# corex.net
KiCad netlist of a schematic drawn in EAGLE
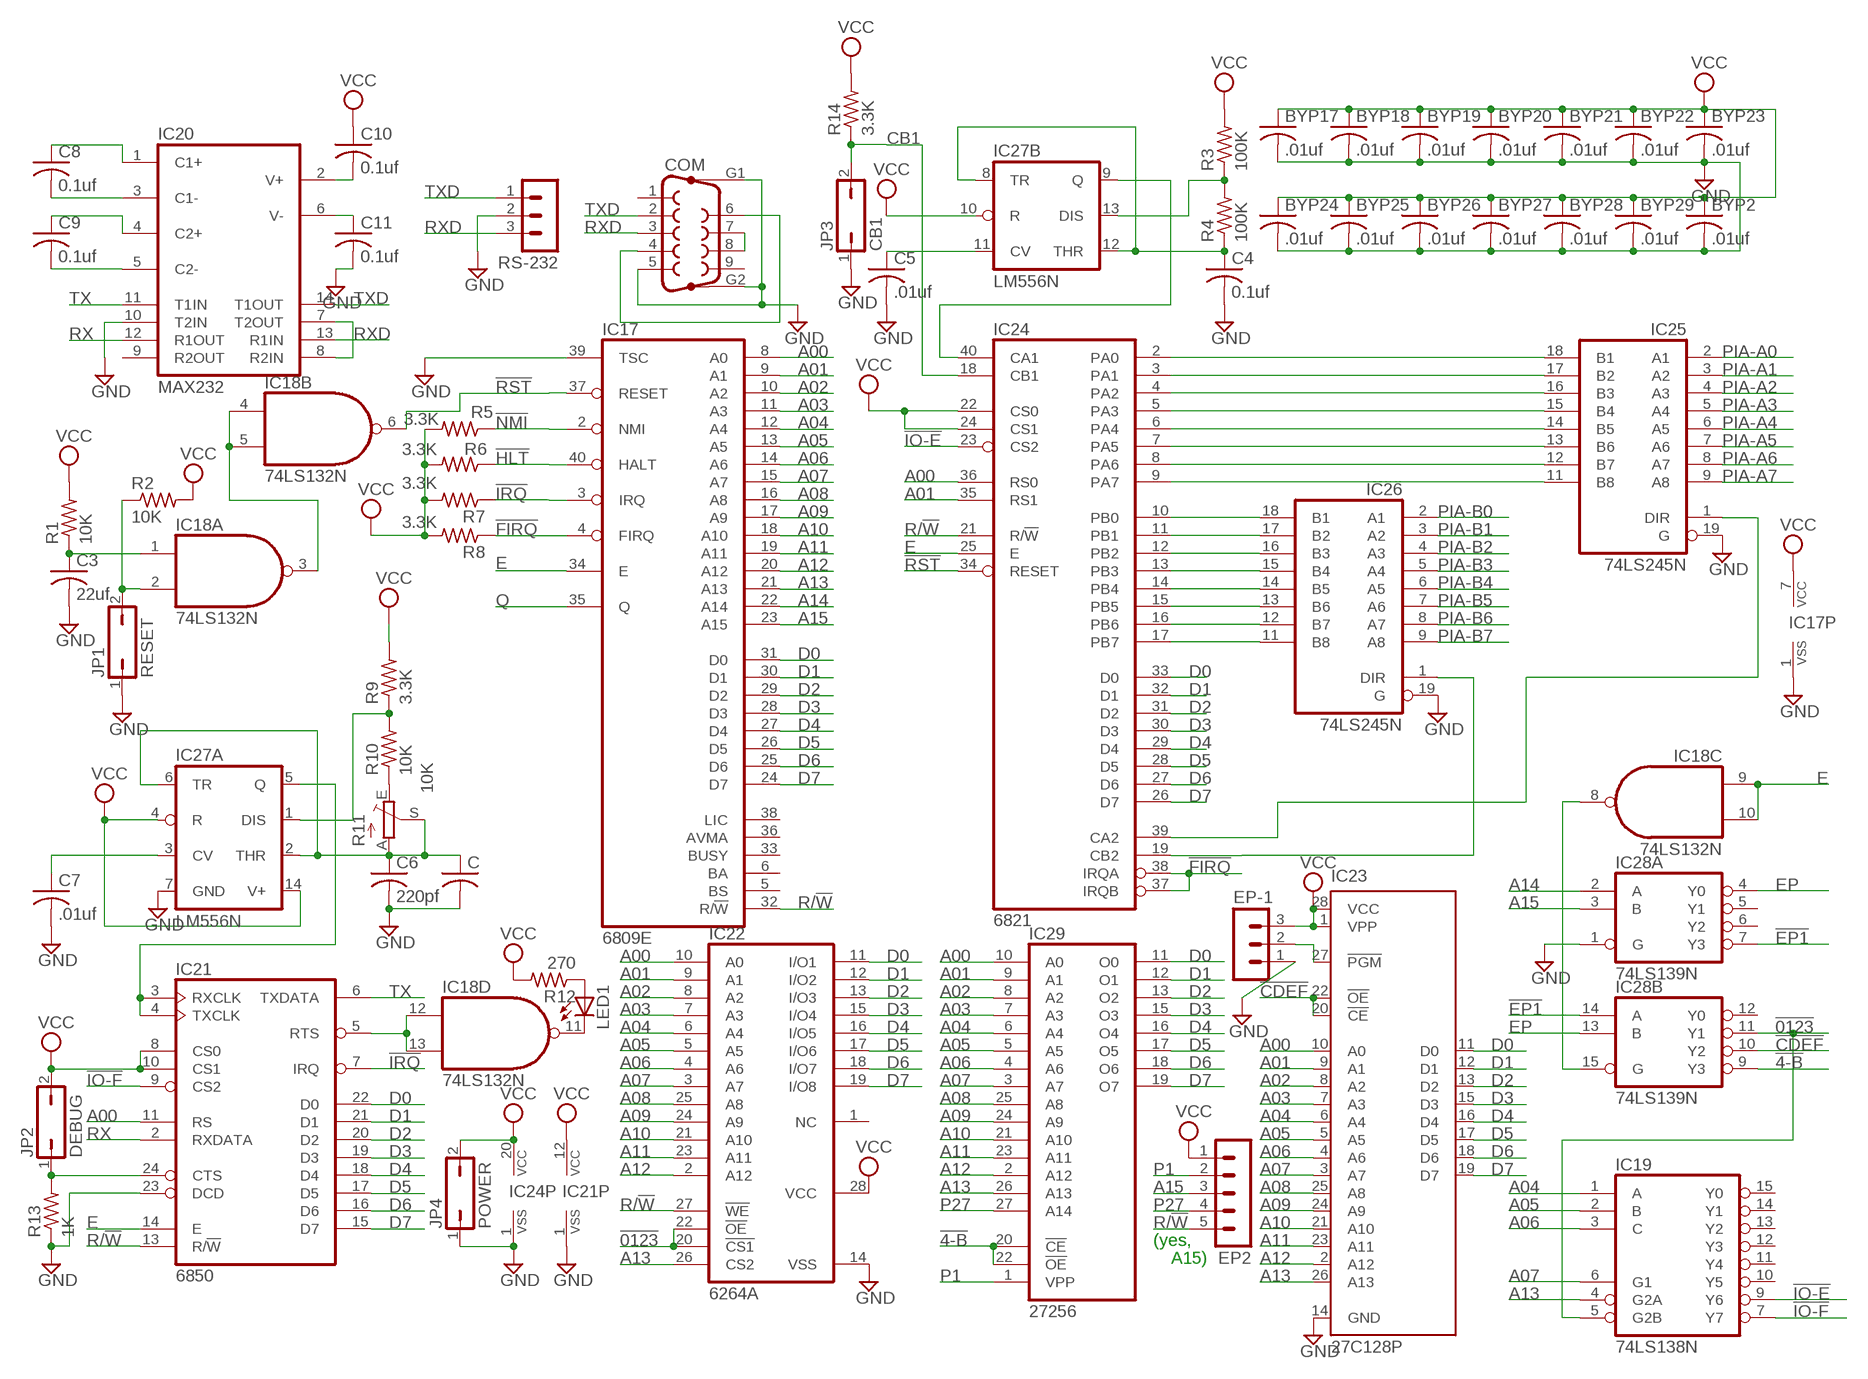
[diagram p0: schematic, sheet 1]
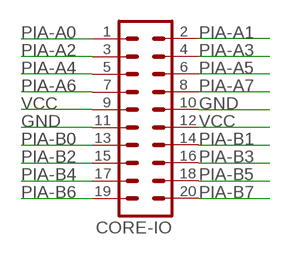
[diagram p1: schematic, sheet 2]
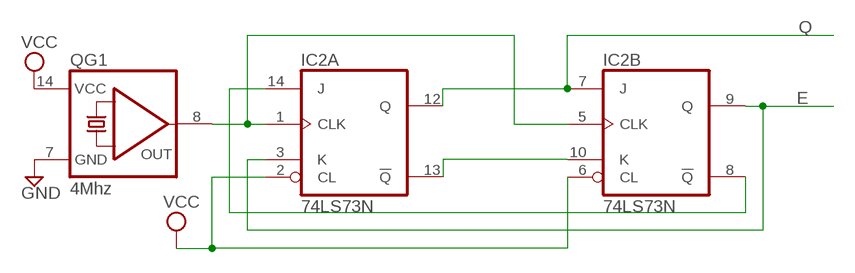
[diagram p2: schematic, sheet 3]

(export (version "E")
  (design (tool "Eeschema 10.0.6"))
  (components
    (comp (ref "IC2")
      (value "74LS73N")
      (footprint "eagle-import:DIL14")
      (libsource (lib "eagle-import") (part "7473NLS"))
    )
    (comp (ref "QG1")
      (value "4Mhz")
      (footprint "eagle-import:DIL14S")
      (libsource (lib "eagle-import") (part "QG5860"))
    )
    (comp (ref "BYP2")
      (value ".01uf")
      (footprint "eagle-import:C050-025X075")
      (libsource (lib "eagle-import") (part "C-US050-025X075"))
    )
    (comp (ref "BYP17")
      (value ".01uf")
      (footprint "eagle-import:C050-025X075")
      (libsource (lib "eagle-import") (part "C-US050-025X075"))
    )
    (comp (ref "BYP18")
      (value ".01uf")
      (footprint "eagle-import:C050-025X075")
      (libsource (lib "eagle-import") (part "C-US050-025X075"))
    )
    (comp (ref "BYP19")
      (value ".01uf")
      (footprint "eagle-import:C050-025X075")
      (libsource (lib "eagle-import") (part "C-US050-025X075"))
    )
    (comp (ref "BYP20")
      (value ".01uf")
      (footprint "eagle-import:C050-025X075")
      (libsource (lib "eagle-import") (part "C-US050-025X075"))
    )
    (comp (ref "BYP21")
      (value ".01uf")
      (footprint "eagle-import:C050-025X075")
      (libsource (lib "eagle-import") (part "C-US050-025X075"))
    )
    (comp (ref "BYP22")
      (value ".01uf")
      (footprint "eagle-import:C050-025X075")
      (libsource (lib "eagle-import") (part "C-US050-025X075"))
    )
    (comp (ref "BYP23")
      (value ".01uf")
      (footprint "eagle-import:C050-025X075")
      (libsource (lib "eagle-import") (part "C-US050-025X075"))
    )
    (comp (ref "BYP24")
      (value ".01uf")
      (footprint "eagle-import:C050-025X075")
      (libsource (lib "eagle-import") (part "C-US050-025X075"))
    )
    (comp (ref "BYP25")
      (value ".01uf")
      (footprint "eagle-import:C050-025X075")
      (libsource (lib "eagle-import") (part "C-US050-025X075"))
    )
    (comp (ref "BYP26")
      (value ".01uf")
      (footprint "eagle-import:C050-025X075")
      (libsource (lib "eagle-import") (part "C-US050-025X075"))
    )
    (comp (ref "BYP27")
      (value ".01uf")
      (footprint "eagle-import:C050-025X075")
      (libsource (lib "eagle-import") (part "C-US050-025X075"))
    )
    (comp (ref "BYP28")
      (value ".01uf")
      (footprint "eagle-import:C050-025X075")
      (libsource (lib "eagle-import") (part "C-US050-025X075"))
    )
    (comp (ref "BYP29")
      (value ".01uf")
      (footprint "eagle-import:C050-025X075")
      (libsource (lib "eagle-import") (part "C-US050-025X075"))
    )
    (comp (ref "C")
      (value "C-US050-025X075")
      (footprint "eagle-import:C050-025X075")
      (libsource (lib "eagle-import") (part "C-US050-025X075"))
    )
    (comp (ref "C3")
      (value "22uf")
      (footprint "eagle-import:C102-054X133")
      (libsource (lib "eagle-import") (part "C-US102-054X133"))
    )
    (comp (ref "C4")
      (value "0.1uf")
      (footprint "eagle-import:C050-025X075")
      (libsource (lib "eagle-import") (part "C-US050-025X075"))
    )
    (comp (ref "C5")
      (value ".01uf")
      (footprint "eagle-import:C050-025X075")
      (libsource (lib "eagle-import") (part "C-US050-025X075"))
    )
    (comp (ref "C6")
      (value "220pf")
      (footprint "eagle-import:C050-025X075")
      (libsource (lib "eagle-import") (part "C-US050-025X075"))
    )
    (comp (ref "C7")
      (value ".01uf")
      (footprint "eagle-import:C050-025X075")
      (libsource (lib "eagle-import") (part "C-US050-025X075"))
    )
    (comp (ref "C8")
      (value "0.1uf")
      (footprint "eagle-import:C050-025X075")
      (libsource (lib "eagle-import") (part "C-US050-025X075"))
    )
    (comp (ref "C9")
      (value "0.1uf")
      (footprint "eagle-import:C050-025X075")
      (libsource (lib "eagle-import") (part "C-US050-025X075"))
    )
    (comp (ref "C10")
      (value "0.1uf")
      (footprint "eagle-import:C050-025X075")
      (libsource (lib "eagle-import") (part "C-US050-025X075"))
    )
    (comp (ref "C11")
      (value "0.1uf")
      (footprint "eagle-import:C050-025X075")
      (libsource (lib "eagle-import") (part "C-US050-025X075"))
    )
    (comp (ref "COM")
      (value "F09HP")
      (footprint "eagle-import:F09HP")
      (libsource (lib "eagle-import") (part "F09HP"))
    )
    (comp (ref "EP-1")
      (value "MA03-1")
      (footprint "eagle-import:MA03-1")
      (libsource (lib "eagle-import") (part "MA03-1"))
    )
    (comp (ref "EP2")
      (value "MA05-1")
      (footprint "eagle-import:MA05-1")
      (libsource (lib "eagle-import") (part "MA05-1"))
    )
    (comp (ref "IC17")
      (value "6809E")
      (footprint "eagle-import:DIL40")
      (fields (field (name "MF") "NTE ELECTRONICS") (field (name "MPN") "NTE6809E"))
      (libsource (lib "eagle-import") (part "6809E"))
    )
    (comp (ref "IC18")
      (value "74LS132N")
      (footprint "eagle-import:DIL14")
      (libsource (lib "eagle-import") (part "7400NLS"))
    )
    (comp (ref "IC19")
      (value "74LS138N")
      (footprint "eagle-import:DIL16")
      (libsource (lib "eagle-import") (part "74138NLS"))
    )
    (comp (ref "IC20")
      (value "MAX232")
      (footprint "eagle-import:DIL16")
      (fields (field (name "MF") "MAXIM") (field (name "MPN") "MAX232ACPE+"))
      (libsource (lib "eagle-import") (part "MAX232"))
    )
    (comp (ref "IC21")
      (value "6850")
      (footprint "eagle-import:DIL24")
      (fields (field (name "MF") "NTE ELECTRONICS") (field (name "MPN") "NTE6850"))
      (libsource (lib "eagle-import") (part "6850"))
    )
    (comp (ref "IC22")
      (value "6264A")
      (footprint "eagle-import:DIL28-6")
      (libsource (lib "eagle-import") (part "6264A"))
    )
    (comp (ref "IC23")
      (value "27C128P")
      (footprint "eagle-import:DIL28-6")
      (libsource (lib "eagle-import") (part "27128PC"))
    )
    (comp (ref "IC24")
      (value "6821")
      (footprint "eagle-import:DIL40")
      (fields (field (name "MF") "NTE ELECTRONICS") (field (name "MPN") "NTE6821"))
      (libsource (lib "eagle-import") (part "6821"))
    )
    (comp (ref "IC25")
      (value "74LS245N")
      (footprint "eagle-import:DIL20")
      (libsource (lib "eagle-import") (part "74245NLS"))
    )
    (comp (ref "IC26")
      (value "74LS245N")
      (footprint "eagle-import:DIL20")
      (libsource (lib "eagle-import") (part "74245NLS"))
    )
    (comp (ref "IC27")
      (value "LM556N")
      (footprint "eagle-import:DIL14")
      (libsource (lib "eagle-import") (part "556NLM"))
    )
    (comp (ref "IC28")
      (value "74LS139N")
      (footprint "eagle-import:DIL16")
      (libsource (lib "eagle-import") (part "74139NLS"))
    )
    (comp (ref "IC29")
      (value "27256")
      (footprint "eagle-import:DIL28")
      (libsource (lib "eagle-import") (part "27256"))
    )
    (comp (ref "JP1")
      (value "RESET")
      (footprint "eagle-import:JP1")
      (libsource (lib "eagle-import") (part "JP1Q"))
    )
    (comp (ref "JP2")
      (value "DEBUG")
      (footprint "eagle-import:JP1")
      (libsource (lib "eagle-import") (part "JP1Q"))
    )
    (comp (ref "JP3")
      (value "CB1")
      (footprint "eagle-import:JP1")
      (libsource (lib "eagle-import") (part "JP1Q"))
    )
    (comp (ref "JP4")
      (value "POWER")
      (footprint "eagle-import:JP1")
      (libsource (lib "eagle-import") (part "JP1Q"))
    )
    (comp (ref "LED1")
      (value "LED3MM")
      (footprint "eagle-import:LED3MM")
      (libsource (lib "eagle-import") (part "LED3MM"))
    )
    (comp (ref "R1")
      (value "10K")
      (footprint "eagle-import:0207_7")
      (libsource (lib "eagle-import") (part "R-US_0207/7"))
    )
    (comp (ref "R2")
      (value "10K")
      (footprint "eagle-import:0207_7")
      (libsource (lib "eagle-import") (part "R-US_0207/7"))
    )
    (comp (ref "R3")
      (value "100K")
      (footprint "eagle-import:0207_7")
      (libsource (lib "eagle-import") (part "R-US_0207/7"))
    )
    (comp (ref "R4")
      (value "100K")
      (footprint "eagle-import:0207_7")
      (libsource (lib "eagle-import") (part "R-US_0207/7"))
    )
    (comp (ref "R5")
      (value "3.3K")
      (footprint "eagle-import:0207_7")
      (libsource (lib "eagle-import") (part "R-US_0207/7"))
    )
    (comp (ref "R6")
      (value "3.3K")
      (footprint "eagle-import:0207_7")
      (libsource (lib "eagle-import") (part "R-US_0207/7"))
    )
    (comp (ref "R7")
      (value "3.3K")
      (footprint "eagle-import:0207_7")
      (libsource (lib "eagle-import") (part "R-US_0207/7"))
    )
    (comp (ref "R8")
      (value "3.3K")
      (footprint "eagle-import:0207_7")
      (libsource (lib "eagle-import") (part "R-US_0207/7"))
    )
    (comp (ref "R9")
      (value "3.3K")
      (footprint "eagle-import:0207_7")
      (libsource (lib "eagle-import") (part "R-US_0207/7"))
    )
    (comp (ref "R10")
      (value "10K")
      (footprint "eagle-import:0207_7")
      (libsource (lib "eagle-import") (part "R-US_0207/7"))
    )
    (comp (ref "R11")
      (value "10K")
      (footprint "eagle-import:SP19L")
      (libsource (lib "eagle-import") (part "TRIM_EU-B90P"))
    )
    (comp (ref "R12")
      (value "270")
      (footprint "eagle-import:0207_7")
      (libsource (lib "eagle-import") (part "R-US_0207/7"))
    )
    (comp (ref "R13")
      (value "1K")
      (footprint "eagle-import:0207_7")
      (libsource (lib "eagle-import") (part "R-US_0207/7"))
    )
    (comp (ref "R14")
      (value "3.3K")
      (footprint "eagle-import:0207_7")
      (libsource (lib "eagle-import") (part "R-US_0207/7"))
    )
    (comp (ref "RS-232")
      (value "MA03-1")
      (footprint "eagle-import:MA03-1")
      (libsource (lib "eagle-import") (part "MA03-1"))
    )
    (comp (ref "CORE-IO")
      (value "MA10-2")
      (footprint "eagle-import:MA10-2")
      (libsource (lib "eagle-import") (part "MA10-2"))
    )
  )
  (nets
    (net (code "1") (name "A00") (class "Default")
      (node (ref "IC17") (pin "8") (pinfunction "A0_8") (pintype "tri_state"))
      (node (ref "IC21") (pin "11") (pinfunction "RS_11") (pintype "input"))
      (node (ref "IC22") (pin "10") (pinfunction "A0_10") (pintype "input"))
      (node (ref "IC23") (pin "10") (pinfunction "A0_10") (pintype "input"))
      (node (ref "IC24") (pin "36") (pinfunction "RS0_36") (pintype "input"))
      (node (ref "IC29") (pin "10") (pinfunction "A0_10") (pintype "input"))
    )
    (net (code "2") (name "A01") (class "Default")
      (node (ref "IC17") (pin "9") (pinfunction "A1_9") (pintype "tri_state"))
      (node (ref "IC22") (pin "9") (pinfunction "A1_9") (pintype "input"))
      (node (ref "IC23") (pin "9") (pinfunction "A1_9") (pintype "input"))
      (node (ref "IC24") (pin "35") (pinfunction "RS1_35") (pintype "input"))
      (node (ref "IC29") (pin "9") (pinfunction "A1_9") (pintype "input"))
    )
    (net (code "3") (name "A02") (class "Default")
      (node (ref "IC17") (pin "10") (pinfunction "A2_10") (pintype "tri_state"))
      (node (ref "IC22") (pin "8") (pinfunction "A2_8") (pintype "input"))
      (node (ref "IC23") (pin "8") (pinfunction "A2_8") (pintype "input"))
      (node (ref "IC29") (pin "8") (pinfunction "A2_8") (pintype "input"))
    )
    (net (code "4") (name "A03") (class "Default")
      (node (ref "IC17") (pin "11") (pinfunction "A3_11") (pintype "tri_state"))
      (node (ref "IC22") (pin "7") (pinfunction "A3_7") (pintype "input"))
      (node (ref "IC23") (pin "7") (pinfunction "A3_7") (pintype "input"))
      (node (ref "IC29") (pin "7") (pinfunction "A3_7") (pintype "input"))
    )
    (net (code "5") (name "A04") (class "Default")
      (node (ref "IC17") (pin "12") (pinfunction "A4_12") (pintype "tri_state"))
      (node (ref "IC19") (pin "1") (pinfunction "A_1") (pintype "input"))
      (node (ref "IC22") (pin "6") (pinfunction "A4_6") (pintype "input"))
      (node (ref "IC23") (pin "6") (pinfunction "A4_6") (pintype "input"))
      (node (ref "IC29") (pin "6") (pinfunction "A4_6") (pintype "input"))
    )
    (net (code "6") (name "A05") (class "Default")
      (node (ref "IC17") (pin "13") (pinfunction "A5_13") (pintype "tri_state"))
      (node (ref "IC19") (pin "2") (pinfunction "B_2") (pintype "input"))
      (node (ref "IC22") (pin "5") (pinfunction "A5_5") (pintype "input"))
      (node (ref "IC23") (pin "5") (pinfunction "A5_5") (pintype "input"))
      (node (ref "IC29") (pin "5") (pinfunction "A5_5") (pintype "input"))
    )
    (net (code "7") (name "A06") (class "Default")
      (node (ref "IC17") (pin "14") (pinfunction "A6_14") (pintype "tri_state"))
      (node (ref "IC19") (pin "3") (pinfunction "C_3") (pintype "input"))
      (node (ref "IC22") (pin "4") (pinfunction "A6_4") (pintype "input"))
      (node (ref "IC23") (pin "4") (pinfunction "A6_4") (pintype "input"))
      (node (ref "IC29") (pin "4") (pinfunction "A6_4") (pintype "input"))
    )
    (net (code "8") (name "A07") (class "Default")
      (node (ref "IC17") (pin "15") (pinfunction "A7_15") (pintype "tri_state"))
      (node (ref "IC19") (pin "6") (pinfunction "G1_6") (pintype "input"))
      (node (ref "IC22") (pin "3") (pinfunction "A7_3") (pintype "input"))
      (node (ref "IC23") (pin "3") (pinfunction "A7_3") (pintype "input"))
      (node (ref "IC29") (pin "3") (pinfunction "A7_3") (pintype "input"))
    )
    (net (code "9") (name "A08") (class "Default")
      (node (ref "IC17") (pin "16") (pinfunction "A8_16") (pintype "tri_state"))
      (node (ref "IC22") (pin "25") (pinfunction "A8_25") (pintype "input"))
      (node (ref "IC23") (pin "25") (pinfunction "A8_25") (pintype "input"))
      (node (ref "IC29") (pin "25") (pinfunction "A8_25") (pintype "input"))
    )
    (net (code "10") (name "A09") (class "Default")
      (node (ref "IC17") (pin "17") (pinfunction "A9_17") (pintype "tri_state"))
      (node (ref "IC22") (pin "24") (pinfunction "A9_24") (pintype "input"))
      (node (ref "IC23") (pin "24") (pinfunction "A9_24") (pintype "input"))
      (node (ref "IC29") (pin "24") (pinfunction "A9_24") (pintype "input"))
    )
    (net (code "11") (name "A10") (class "Default")
      (node (ref "IC17") (pin "18") (pinfunction "A10_18") (pintype "tri_state"))
      (node (ref "IC22") (pin "21") (pinfunction "A10_21") (pintype "input"))
      (node (ref "IC23") (pin "21") (pinfunction "A10_21") (pintype "input"))
      (node (ref "IC29") (pin "21") (pinfunction "A10_21") (pintype "input"))
    )
    (net (code "12") (name "A11") (class "Default")
      (node (ref "IC17") (pin "19") (pinfunction "A11_19") (pintype "tri_state"))
      (node (ref "IC22") (pin "23") (pinfunction "A11_23") (pintype "input"))
      (node (ref "IC23") (pin "23") (pinfunction "A11_23") (pintype "input"))
      (node (ref "IC29") (pin "23") (pinfunction "A11_23") (pintype "input"))
    )
    (net (code "13") (name "A12") (class "Default")
      (node (ref "IC17") (pin "20") (pinfunction "A12_20") (pintype "tri_state"))
      (node (ref "IC22") (pin "2") (pinfunction "A12_2") (pintype "input"))
      (node (ref "IC23") (pin "2") (pinfunction "A12_2") (pintype "input"))
      (node (ref "IC29") (pin "2") (pinfunction "A12_2") (pintype "input"))
    )
    (net (code "14") (name "A13") (class "Default")
      (node (ref "IC17") (pin "21") (pinfunction "A13_21") (pintype "tri_state"))
      (node (ref "IC19") (pin "4") (pinfunction "G2A_4") (pintype "input"))
      (node (ref "IC22") (pin "26") (pinfunction "CS2_26") (pintype "input"))
      (node (ref "IC23") (pin "26") (pinfunction "A13_26") (pintype "input"))
      (node (ref "IC29") (pin "26") (pinfunction "A13_26") (pintype "input"))
    )
    (net (code "15") (name "A14") (class "Default")
      (node (ref "IC17") (pin "22") (pinfunction "A14_22") (pintype "tri_state"))
      (node (ref "IC28") (pin "2") (pinfunction "A_2") (pintype "input"))
    )
    (net (code "16") (name "A15") (class "Default")
      (node (ref "EP2") (pin "3") (pinfunction "3_3") (pintype "passive"))
      (node (ref "IC17") (pin "23") (pinfunction "A15_23") (pintype "tri_state"))
      (node (ref "IC28") (pin "3") (pinfunction "B_3") (pintype "input"))
    )
    (net (code "17") (name "CB1") (class "Default")
      (node (ref "IC24") (pin "18") (pinfunction "CB1_18") (pintype "input"))
      (node (ref "JP3") (pin "2") (pinfunction "2_2") (pintype "passive"))
      (node (ref "R14") (pin "1") (pinfunction "1_1") (pintype "passive"))
    )
    (net (code "18") (name "D0") (class "Default")
      (node (ref "IC17") (pin "31") (pinfunction "D0_31") (pintype "bidirectional"))
      (node (ref "IC21") (pin "22") (pinfunction "D0_22") (pintype "bidirectional"))
      (node (ref "IC22") (pin "11") (pinfunction "I/O1_11") (pintype "bidirectional"))
      (node (ref "IC23") (pin "11") (pinfunction "D0_11") (pintype "tri_state"))
      (node (ref "IC24") (pin "33") (pinfunction "D0_33") (pintype "bidirectional"))
      (node (ref "IC29") (pin "11") (pinfunction "O0_11") (pintype "tri_state"))
    )
    (net (code "19") (name "D1") (class "Default")
      (node (ref "IC17") (pin "30") (pinfunction "D1_30") (pintype "bidirectional"))
      (node (ref "IC21") (pin "21") (pinfunction "D1_21") (pintype "bidirectional"))
      (node (ref "IC22") (pin "12") (pinfunction "I/O2_12") (pintype "bidirectional"))
      (node (ref "IC23") (pin "12") (pinfunction "D1_12") (pintype "tri_state"))
      (node (ref "IC24") (pin "32") (pinfunction "D1_32") (pintype "bidirectional"))
      (node (ref "IC29") (pin "12") (pinfunction "O1_12") (pintype "tri_state"))
    )
    (net (code "20") (name "D2") (class "Default")
      (node (ref "IC17") (pin "29") (pinfunction "D2_29") (pintype "bidirectional"))
      (node (ref "IC21") (pin "20") (pinfunction "D2_20") (pintype "bidirectional"))
      (node (ref "IC22") (pin "13") (pinfunction "I/O3_13") (pintype "bidirectional"))
      (node (ref "IC23") (pin "13") (pinfunction "D2_13") (pintype "tri_state"))
      (node (ref "IC24") (pin "31") (pinfunction "D2_31") (pintype "bidirectional"))
      (node (ref "IC29") (pin "13") (pinfunction "O2_13") (pintype "tri_state"))
    )
    (net (code "21") (name "D3") (class "Default")
      (node (ref "IC17") (pin "28") (pinfunction "D3_28") (pintype "bidirectional"))
      (node (ref "IC21") (pin "19") (pinfunction "D3_19") (pintype "bidirectional"))
      (node (ref "IC22") (pin "15") (pinfunction "I/O4_15") (pintype "bidirectional"))
      (node (ref "IC23") (pin "15") (pinfunction "D3_15") (pintype "tri_state"))
      (node (ref "IC24") (pin "30") (pinfunction "D3_30") (pintype "bidirectional"))
      (node (ref "IC29") (pin "15") (pinfunction "O3_15") (pintype "tri_state"))
    )
    (net (code "22") (name "D4") (class "Default")
      (node (ref "IC17") (pin "27") (pinfunction "D4_27") (pintype "bidirectional"))
      (node (ref "IC21") (pin "18") (pinfunction "D4_18") (pintype "bidirectional"))
      (node (ref "IC22") (pin "16") (pinfunction "I/O5_16") (pintype "bidirectional"))
      (node (ref "IC23") (pin "16") (pinfunction "D4_16") (pintype "tri_state"))
      (node (ref "IC24") (pin "29") (pinfunction "D4_29") (pintype "bidirectional"))
      (node (ref "IC29") (pin "16") (pinfunction "O4_16") (pintype "tri_state"))
    )
    (net (code "23") (name "D5") (class "Default")
      (node (ref "IC17") (pin "26") (pinfunction "D5_26") (pintype "bidirectional"))
      (node (ref "IC21") (pin "17") (pinfunction "D5_17") (pintype "bidirectional"))
      (node (ref "IC22") (pin "17") (pinfunction "I/O6_17") (pintype "bidirectional"))
      (node (ref "IC23") (pin "17") (pinfunction "D5_17") (pintype "tri_state"))
      (node (ref "IC24") (pin "28") (pinfunction "D5_28") (pintype "bidirectional"))
      (node (ref "IC29") (pin "17") (pinfunction "O5_17") (pintype "tri_state"))
    )
    (net (code "24") (name "D6") (class "Default")
      (node (ref "IC17") (pin "25") (pinfunction "D6_25") (pintype "bidirectional"))
      (node (ref "IC21") (pin "16") (pinfunction "D6_16") (pintype "bidirectional"))
      (node (ref "IC22") (pin "18") (pinfunction "I/O7_18") (pintype "bidirectional"))
      (node (ref "IC23") (pin "18") (pinfunction "D6_18") (pintype "tri_state"))
      (node (ref "IC24") (pin "27") (pinfunction "D6_27") (pintype "bidirectional"))
      (node (ref "IC29") (pin "18") (pinfunction "O6_18") (pintype "tri_state"))
    )
    (net (code "25") (name "D7") (class "Default")
      (node (ref "IC17") (pin "24") (pinfunction "D7_24") (pintype "bidirectional"))
      (node (ref "IC21") (pin "15") (pinfunction "D7_15") (pintype "bidirectional"))
      (node (ref "IC22") (pin "19") (pinfunction "I/O8_19") (pintype "bidirectional"))
      (node (ref "IC23") (pin "19") (pinfunction "D7_19") (pintype "tri_state"))
      (node (ref "IC24") (pin "26") (pinfunction "D7_26") (pintype "bidirectional"))
      (node (ref "IC29") (pin "19") (pinfunction "O7_19") (pintype "tri_state"))
    )
    (net (code "26") (name "E") (class "Default")
      (node (ref "IC17") (pin "34") (pinfunction "E_34") (pintype "input"))
      (node (ref "IC18") (pin "10") (pinfunction "I1_10") (pintype "input"))
      (node (ref "IC18") (pin "9") (pinfunction "I0_9") (pintype "input"))
      (node (ref "IC2") (pin "3") (pinfunction "K_3") (pintype "input"))
      (node (ref "IC2") (pin "9") (pinfunction "Q_9") (pintype "output"))
      (node (ref "IC21") (pin "14") (pinfunction "E_14") (pintype "input"))
      (node (ref "IC24") (pin "25") (pinfunction "E_25") (pintype "input"))
    )
    (net (code "27") (name "EP") (class "Default")
      (node (ref "IC28") (pin "13") (pinfunction "B_13") (pintype "input"))
      (node (ref "IC28") (pin "4") (pinfunction "Y0_4") (pintype "output"))
    )
    (net (code "28") (name "GND") (class "Default")
      (node (ref "BYP17") (pin "2") (pinfunction "2_2") (pintype "passive"))
      (node (ref "BYP18") (pin "2") (pinfunction "2_2") (pintype "passive"))
      (node (ref "BYP19") (pin "2") (pinfunction "2_2") (pintype "passive"))
      (node (ref "BYP2") (pin "2") (pinfunction "2_2") (pintype "passive"))
      (node (ref "BYP20") (pin "2") (pinfunction "2_2") (pintype "passive"))
      (node (ref "BYP21") (pin "2") (pinfunction "2_2") (pintype "passive"))
      (node (ref "BYP22") (pin "2") (pinfunction "2_2") (pintype "passive"))
      (node (ref "BYP23") (pin "2") (pinfunction "2_2") (pintype "passive"))
      (node (ref "BYP24") (pin "2") (pinfunction "2_2") (pintype "passive"))
      (node (ref "BYP25") (pin "2") (pinfunction "2_2") (pintype "passive"))
      (node (ref "BYP26") (pin "2") (pinfunction "2_2") (pintype "passive"))
      (node (ref "BYP27") (pin "2") (pinfunction "2_2") (pintype "passive"))
      (node (ref "BYP28") (pin "2") (pinfunction "2_2") (pintype "passive"))
      (node (ref "BYP29") (pin "2") (pinfunction "2_2") (pintype "passive"))
      (node (ref "C") (pin "2") (pinfunction "2_2") (pintype "passive"))
      (node (ref "C11") (pin "2") (pinfunction "2_2") (pintype "passive"))
      (node (ref "C3") (pin "2") (pinfunction "2_2") (pintype "passive"))
      (node (ref "C4") (pin "2") (pinfunction "2_2") (pintype "passive"))
      (node (ref "C5") (pin "2") (pinfunction "2_2") (pintype "passive"))
      (node (ref "C6") (pin "2") (pinfunction "2_2") (pintype "passive"))
      (node (ref "C7") (pin "2") (pinfunction "2_2") (pintype "passive"))
      (node (ref "COM") (pin "5") (pinfunction "5_5") (pintype "passive"))
      (node (ref "COM") (pin "G1") (pinfunction "G1_G1") (pintype "passive"))
      (node (ref "COM") (pin "G2") (pinfunction "G2_G2") (pintype "passive"))
      (node (ref "CORE-IO") (pin "10") (pinfunction "10_10") (pintype "passive"))
      (node (ref "CORE-IO") (pin "11") (pinfunction "11_11") (pintype "passive"))
      (node (ref "EP-1") (pin "1") (pinfunction "1_1") (pintype "passive"))
      (node (ref "IC17") (pin "1") (pinfunction "VSS_1") (pintype "power_in"))
      (node (ref "IC17") (pin "39") (pinfunction "TSC_39") (pintype "input"))
      (node (ref "IC20") (pin "10") (pinfunction "T2IN_10") (pintype "input"))
      (node (ref "IC21") (pin "1") (pinfunction "VSS_1") (pintype "power_in"))
      (node (ref "IC21") (pin "23") (pinfunction "DCD_23") (pintype "input"))
      (node (ref "IC22") (pin "14") (pinfunction "VSS_14") (pintype "power_in"))
      (node (ref "IC23") (pin "14") (pinfunction "GND_14") (pintype "power_in"))
      (node (ref "IC24") (pin "1") (pinfunction "VSS_1") (pintype "power_in"))
      (node (ref "IC25") (pin "19") (pinfunction "G_19") (pintype "input"))
      (node (ref "IC26") (pin "19") (pinfunction "G_19") (pintype "input"))
      (node (ref "IC27") (pin "7") (pinfunction "GND_7") (pintype "power_in"))
      (node (ref "IC28") (pin "1") (pinfunction "G_1") (pintype "input"))
      (node (ref "JP1") (pin "1") (pinfunction "1_1") (pintype "passive"))
      (node (ref "JP3") (pin "1") (pinfunction "1_1") (pintype "passive"))
      (node (ref "JP4") (pin "1") (pinfunction "1_1") (pintype "passive"))
      (node (ref "QG1") (pin "7") (pinfunction "GND_7") (pintype "power_in"))
      (node (ref "R13") (pin "1") (pinfunction "1_1") (pintype "passive"))
      (node (ref "RS-232") (pin "2") (pinfunction "2_2") (pintype "passive"))
    )
    (net (code "29") (name "Net-(COM-Pad4)") (class "Default")
      (node (ref "COM") (pin "4") (pinfunction "4_4") (pintype "passive"))
      (node (ref "COM") (pin "6") (pinfunction "6_6") (pintype "passive"))
    )
    (net (code "30") (name "Net-(COM-Pad7)") (class "Default")
      (node (ref "COM") (pin "7") (pinfunction "7_7") (pintype "passive"))
      (node (ref "COM") (pin "8") (pinfunction "8_8") (pintype "passive"))
    )
    (net (code "31") (name "Net-(IC2A-CLK)") (class "Default")
      (node (ref "IC2") (pin "1") (pinfunction "CLK_1") (pintype "input"))
      (node (ref "IC2") (pin "5") (pinfunction "CLK_5") (pintype "input"))
      (node (ref "QG1") (pin "8") (pinfunction "OUT_8") (pintype "output"))
    )
    (net (code "32") (name "Net-(IC2A-J)") (class "Default")
      (node (ref "IC2") (pin "14") (pinfunction "J_14") (pintype "input"))
      (node (ref "IC2") (pin "8") (pinfunction "~{Q}_8") (pintype "output"))
    )
    (net (code "33") (name "Net-(IC2A-~{Q})") (class "Default")
      (node (ref "IC2") (pin "10") (pinfunction "K_10") (pintype "input"))
      (node (ref "IC2") (pin "13") (pinfunction "~{Q}_13") (pintype "output"))
    )
    (net (code "34") (name "Net-(IC18A-I0)") (class "Default")
      (node (ref "C3") (pin "1") (pinfunction "1_1") (pintype "passive"))
      (node (ref "IC18") (pin "1") (pinfunction "I0_1") (pintype "input"))
      (node (ref "R1") (pin "1") (pinfunction "1_1") (pintype "passive"))
    )
    (net (code "35") (name "Net-(IC18A-I1)") (class "Default")
      (node (ref "IC18") (pin "2") (pinfunction "I1_2") (pintype "input"))
      (node (ref "JP1") (pin "2") (pinfunction "2_2") (pintype "passive"))
      (node (ref "R2") (pin "1") (pinfunction "1_1") (pintype "passive"))
    )
    (net (code "36") (name "Net-(IC18A-O)") (class "Default")
      (node (ref "IC18") (pin "3") (pinfunction "O_3") (pintype "output"))
      (node (ref "IC18") (pin "4") (pinfunction "I0_4") (pintype "input"))
      (node (ref "IC18") (pin "5") (pinfunction "I1_5") (pintype "input"))
    )
    (net (code "37") (name "Net-(IC18C-O)") (class "Default")
      (node (ref "IC18") (pin "8") (pinfunction "O_8") (pintype "output"))
      (node (ref "IC28") (pin "15") (pinfunction "G_15") (pintype "input"))
    )
    (net (code "38") (name "Net-(IC18D-I0)") (class "Default")
      (node (ref "IC18") (pin "12") (pinfunction "I0_12") (pintype "input"))
      (node (ref "IC18") (pin "13") (pinfunction "I1_13") (pintype "input"))
      (node (ref "IC21") (pin "5") (pinfunction "RTS_5") (pintype "output"))
    )
    (net (code "39") (name "Net-(IC18D-O)") (class "Default")
      (node (ref "IC18") (pin "11") (pinfunction "O_11") (pintype "output"))
      (node (ref "LED1") (pin "K") (pinfunction "C_K") (pintype "passive"))
    )
    (net (code "40") (name "Net-(IC20A-C1+)") (class "Default")
      (node (ref "C8") (pin "1") (pinfunction "1_1") (pintype "passive"))
      (node (ref "IC20") (pin "1") (pinfunction "C1+_1") (pintype "bidirectional"))
    )
    (net (code "41") (name "Net-(IC20A-C1-)") (class "Default")
      (node (ref "C8") (pin "2") (pinfunction "2_2") (pintype "passive"))
      (node (ref "IC20") (pin "3") (pinfunction "C1-_3") (pintype "bidirectional"))
    )
    (net (code "42") (name "Net-(IC20A-C2+)") (class "Default")
      (node (ref "C9") (pin "1") (pinfunction "1_1") (pintype "passive"))
      (node (ref "IC20") (pin "4") (pinfunction "C2+_4") (pintype "bidirectional"))
    )
    (net (code "43") (name "Net-(IC20A-C2-)") (class "Default")
      (node (ref "C9") (pin "2") (pinfunction "2_2") (pintype "passive"))
      (node (ref "IC20") (pin "5") (pinfunction "C2-_5") (pintype "bidirectional"))
    )
    (net (code "44") (name "Net-(IC20A-R2IN)") (class "Default")
      (node (ref "IC20") (pin "7") (pinfunction "T2OUT_7") (pintype "output"))
      (node (ref "IC20") (pin "8") (pinfunction "R2IN_8") (pintype "input"))
    )
    (net (code "45") (name "Net-(IC20A-V+)") (class "Default")
      (node (ref "C10") (pin "2") (pinfunction "2_2") (pintype "passive"))
      (node (ref "IC20") (pin "2") (pinfunction "V+_2") (pintype "bidirectional"))
    )
    (net (code "46") (name "Net-(IC20A-V-)") (class "Default")
      (node (ref "C11") (pin "1") (pinfunction "1_1") (pintype "passive"))
      (node (ref "IC20") (pin "6") (pinfunction "V-_6") (pintype "bidirectional"))
    )
    (net (code "47") (name "Net-(IC21A-CTS)") (class "Default")
      (node (ref "IC21") (pin "24") (pinfunction "CTS_24") (pintype "input"))
      (node (ref "JP2") (pin "1") (pinfunction "1_1") (pintype "passive"))
      (node (ref "R13") (pin "2") (pinfunction "2_2") (pintype "passive"))
    )
    (net (code "48") (name "Net-(IC21A-RXCLK)") (class "Default")
      (node (ref "IC21") (pin "3") (pinfunction "RXCLK_3") (pintype "input"))
      (node (ref "IC21") (pin "4") (pinfunction "TXCLK_4") (pintype "input"))
      (node (ref "IC27") (pin "5") (pinfunction "Q_5") (pintype "output"))
    )
    (net (code "49") (name "Net-(IC23-~{PGM})") (class "Default")
      (node (ref "EP-1") (pin "2") (pinfunction "2_2") (pintype "passive"))
      (node (ref "IC23") (pin "27") (pinfunction "~{PGM}_27") (pintype "passive"))
    )
    (net (code "50") (name "Net-(IC24A-CA1)") (class "Default")
      (node (ref "IC24") (pin "40") (pinfunction "CA1_40") (pintype "input"))
      (node (ref "IC27") (pin "9") (pinfunction "Q_9") (pintype "output"))
    )
    (net (code "51") (name "Net-(IC24A-CA2)") (class "Default")
      (node (ref "IC24") (pin "39") (pinfunction "CA2_39") (pintype "bidirectional"))
      (node (ref "IC25") (pin "1") (pinfunction "DIR_1") (pintype "input"))
    )
    (net (code "52") (name "Net-(IC24A-CB2)") (class "Default")
      (node (ref "IC24") (pin "19") (pinfunction "CB2_19") (pintype "bidirectional"))
      (node (ref "IC26") (pin "1") (pinfunction "DIR_1") (pintype "input"))
    )
    (net (code "53") (name "Net-(IC24A-PA0)") (class "Default")
      (node (ref "IC24") (pin "2") (pinfunction "PA0_2") (pintype "bidirectional"))
      (node (ref "IC25") (pin "18") (pinfunction "B1_18") (pintype "bidirectional"))
    )
    (net (code "54") (name "Net-(IC24A-PA1)") (class "Default")
      (node (ref "IC24") (pin "3") (pinfunction "PA1_3") (pintype "bidirectional"))
      (node (ref "IC25") (pin "17") (pinfunction "B2_17") (pintype "bidirectional"))
    )
    (net (code "55") (name "Net-(IC24A-PA2)") (class "Default")
      (node (ref "IC24") (pin "4") (pinfunction "PA2_4") (pintype "bidirectional"))
      (node (ref "IC25") (pin "16") (pinfunction "B3_16") (pintype "bidirectional"))
    )
    (net (code "56") (name "Net-(IC24A-PA3)") (class "Default")
      (node (ref "IC24") (pin "5") (pinfunction "PA3_5") (pintype "bidirectional"))
      (node (ref "IC25") (pin "15") (pinfunction "B4_15") (pintype "bidirectional"))
    )
    (net (code "57") (name "Net-(IC24A-PA4)") (class "Default")
      (node (ref "IC24") (pin "6") (pinfunction "PA4_6") (pintype "bidirectional"))
      (node (ref "IC25") (pin "14") (pinfunction "B5_14") (pintype "bidirectional"))
    )
    (net (code "58") (name "Net-(IC24A-PA5)") (class "Default")
      (node (ref "IC24") (pin "7") (pinfunction "PA5_7") (pintype "bidirectional"))
      (node (ref "IC25") (pin "13") (pinfunction "B6_13") (pintype "bidirectional"))
    )
    (net (code "59") (name "Net-(IC24A-PA6)") (class "Default")
      (node (ref "IC24") (pin "8") (pinfunction "PA6_8") (pintype "bidirectional"))
      (node (ref "IC25") (pin "12") (pinfunction "B7_12") (pintype "bidirectional"))
    )
    (net (code "60") (name "Net-(IC24A-PA7)") (class "Default")
      (node (ref "IC24") (pin "9") (pinfunction "PA7_9") (pintype "bidirectional"))
      (node (ref "IC25") (pin "11") (pinfunction "B8_11") (pintype "bidirectional"))
    )
    (net (code "61") (name "Net-(IC24A-PB0)") (class "Default")
      (node (ref "IC24") (pin "10") (pinfunction "PB0_10") (pintype "bidirectional"))
      (node (ref "IC26") (pin "18") (pinfunction "B1_18") (pintype "bidirectional"))
    )
    (net (code "62") (name "Net-(IC24A-PB1)") (class "Default")
      (node (ref "IC24") (pin "11") (pinfunction "PB1_11") (pintype "bidirectional"))
      (node (ref "IC26") (pin "17") (pinfunction "B2_17") (pintype "bidirectional"))
    )
    (net (code "63") (name "Net-(IC24A-PB2)") (class "Default")
      (node (ref "IC24") (pin "12") (pinfunction "PB2_12") (pintype "bidirectional"))
      (node (ref "IC26") (pin "16") (pinfunction "B3_16") (pintype "bidirectional"))
    )
    (net (code "64") (name "Net-(IC24A-PB3)") (class "Default")
      (node (ref "IC24") (pin "13") (pinfunction "PB3_13") (pintype "bidirectional"))
      (node (ref "IC26") (pin "15") (pinfunction "B4_15") (pintype "bidirectional"))
    )
    (net (code "65") (name "Net-(IC24A-PB4)") (class "Default")
      (node (ref "IC24") (pin "14") (pinfunction "PB4_14") (pintype "bidirectional"))
      (node (ref "IC26") (pin "14") (pinfunction "B5_14") (pintype "bidirectional"))
    )
    (net (code "66") (name "Net-(IC24A-PB5)") (class "Default")
      (node (ref "IC24") (pin "15") (pinfunction "PB5_15") (pintype "bidirectional"))
      (node (ref "IC26") (pin "13") (pinfunction "B6_13") (pintype "bidirectional"))
    )
    (net (code "67") (name "Net-(IC24A-PB6)") (class "Default")
      (node (ref "IC24") (pin "16") (pinfunction "PB6_16") (pintype "bidirectional"))
      (node (ref "IC26") (pin "12") (pinfunction "B7_12") (pintype "bidirectional"))
    )
    (net (code "68") (name "Net-(IC24A-PB7)") (class "Default")
      (node (ref "IC24") (pin "17") (pinfunction "PB7_17") (pintype "bidirectional"))
      (node (ref "IC26") (pin "11") (pinfunction "B8_11") (pintype "bidirectional"))
    )
    (net (code "69") (name "Net-(IC27A-CV)") (class "Default")
      (node (ref "C7") (pin "1") (pinfunction "1_1") (pintype "passive"))
      (node (ref "IC27") (pin "3") (pinfunction "CV_3") (pintype "input"))
    )
    (net (code "70") (name "Net-(IC27A-DIS)") (class "Default")
      (node (ref "IC27") (pin "1") (pinfunction "DIS_1") (pintype "input"))
      (node (ref "R10") (pin "2") (pinfunction "2_2") (pintype "passive"))
      (node (ref "R9") (pin "1") (pinfunction "1_1") (pintype "passive"))
    )
    (net (code "71") (name "Net-(IC27A-THR)") (class "Default")
      (node (ref "C") (pin "1") (pinfunction "1_1") (pintype "passive"))
      (node (ref "C6") (pin "1") (pinfunction "1_1") (pintype "passive"))
      (node (ref "IC27") (pin "2") (pinfunction "THR_2") (pintype "input"))
      (node (ref "IC27") (pin "6") (pinfunction "TR_6") (pintype "input"))
      (node (ref "R11") (pin "A") (pinfunction "A_A") (pintype "passive"))
      (node (ref "R11") (pin "S") (pinfunction "S_S") (pintype "passive"))
    )
    (net (code "72") (name "Net-(IC27B-CV)") (class "Default")
      (node (ref "C5") (pin "1") (pinfunction "1_1") (pintype "passive"))
      (node (ref "IC27") (pin "11") (pinfunction "CV_11") (pintype "input"))
    )
    (net (code "73") (name "Net-(IC27B-DIS)") (class "Default")
      (node (ref "IC27") (pin "13") (pinfunction "DIS_13") (pintype "input"))
      (node (ref "R3") (pin "1") (pinfunction "1_1") (pintype "passive"))
      (node (ref "R4") (pin "2") (pinfunction "2_2") (pintype "passive"))
    )
    (net (code "74") (name "Net-(IC27B-THR)") (class "Default")
      (node (ref "C4") (pin "1") (pinfunction "1_1") (pintype "passive"))
      (node (ref "IC27") (pin "12") (pinfunction "THR_12") (pintype "input"))
      (node (ref "IC27") (pin "8") (pinfunction "TR_8") (pintype "input"))
      (node (ref "R4") (pin "1") (pinfunction "1_1") (pintype "passive"))
    )
    (net (code "75") (name "Net-(LED1-PadA)") (class "Default")
      (node (ref "LED1") (pin "A") (pinfunction "A_A") (pintype "passive"))
      (node (ref "R12") (pin "1") (pinfunction "1_1") (pintype "passive"))
    )
    (net (code "76") (name "Net-(R10-Pad1)") (class "Default")
      (node (ref "R10") (pin "1") (pinfunction "1_1") (pintype "passive"))
      (node (ref "R11") (pin "E") (pinfunction "E_E") (pintype "passive"))
    )
    (net (code "77") (name "P1") (class "Default")
      (node (ref "EP2") (pin "2") (pinfunction "2_2") (pintype "passive"))
      (node (ref "IC29") (pin "1") (pinfunction "VPP_1") (pintype "input"))
    )
    (net (code "78") (name "P27") (class "Default")
      (node (ref "EP2") (pin "4") (pinfunction "4_4") (pintype "passive"))
      (node (ref "IC29") (pin "27") (pinfunction "A14_27") (pintype "input"))
    )
    (net (code "79") (name "PIA-A0") (class "Default")
      (node (ref "CORE-IO") (pin "1") (pinfunction "1_1") (pintype "passive"))
      (node (ref "IC25") (pin "2") (pinfunction "A1_2") (pintype "bidirectional"))
    )
    (net (code "80") (name "PIA-A1") (class "Default")
      (node (ref "CORE-IO") (pin "2") (pinfunction "2_2") (pintype "passive"))
      (node (ref "IC25") (pin "3") (pinfunction "A2_3") (pintype "bidirectional"))
    )
    (net (code "81") (name "PIA-A2") (class "Default")
      (node (ref "CORE-IO") (pin "3") (pinfunction "3_3") (pintype "passive"))
      (node (ref "IC25") (pin "4") (pinfunction "A3_4") (pintype "bidirectional"))
    )
    (net (code "82") (name "PIA-A3") (class "Default")
      (node (ref "CORE-IO") (pin "4") (pinfunction "4_4") (pintype "passive"))
      (node (ref "IC25") (pin "5") (pinfunction "A4_5") (pintype "bidirectional"))
    )
    (net (code "83") (name "PIA-A4") (class "Default")
      (node (ref "CORE-IO") (pin "5") (pinfunction "5_5") (pintype "passive"))
      (node (ref "IC25") (pin "6") (pinfunction "A5_6") (pintype "bidirectional"))
    )
    (net (code "84") (name "PIA-A5") (class "Default")
      (node (ref "CORE-IO") (pin "6") (pinfunction "6_6") (pintype "passive"))
      (node (ref "IC25") (pin "7") (pinfunction "A6_7") (pintype "bidirectional"))
    )
    (net (code "85") (name "PIA-A6") (class "Default")
      (node (ref "CORE-IO") (pin "7") (pinfunction "7_7") (pintype "passive"))
      (node (ref "IC25") (pin "8") (pinfunction "A7_8") (pintype "bidirectional"))
    )
    (net (code "86") (name "PIA-A7") (class "Default")
      (node (ref "CORE-IO") (pin "8") (pinfunction "8_8") (pintype "passive"))
      (node (ref "IC25") (pin "9") (pinfunction "A8_9") (pintype "bidirectional"))
    )
    (net (code "87") (name "PIA-B0") (class "Default")
      (node (ref "CORE-IO") (pin "13") (pinfunction "13_13") (pintype "passive"))
      (node (ref "IC26") (pin "2") (pinfunction "A1_2") (pintype "bidirectional"))
    )
    (net (code "88") (name "PIA-B1") (class "Default")
      (node (ref "CORE-IO") (pin "14") (pinfunction "14_14") (pintype "passive"))
      (node (ref "IC26") (pin "3") (pinfunction "A2_3") (pintype "bidirectional"))
    )
    (net (code "89") (name "PIA-B2") (class "Default")
      (node (ref "CORE-IO") (pin "15") (pinfunction "15_15") (pintype "passive"))
      (node (ref "IC26") (pin "4") (pinfunction "A3_4") (pintype "bidirectional"))
    )
    (net (code "90") (name "PIA-B3") (class "Default")
      (node (ref "CORE-IO") (pin "16") (pinfunction "16_16") (pintype "passive"))
      (node (ref "IC26") (pin "5") (pinfunction "A4_5") (pintype "bidirectional"))
    )
    (net (code "91") (name "PIA-B4") (class "Default")
      (node (ref "CORE-IO") (pin "17") (pinfunction "17_17") (pintype "passive"))
      (node (ref "IC26") (pin "6") (pinfunction "A5_6") (pintype "bidirectional"))
    )
    (net (code "92") (name "PIA-B5") (class "Default")
      (node (ref "CORE-IO") (pin "18") (pinfunction "18_18") (pintype "passive"))
      (node (ref "IC26") (pin "7") (pinfunction "A6_7") (pintype "bidirectional"))
    )
    (net (code "93") (name "PIA-B6") (class "Default")
      (node (ref "CORE-IO") (pin "19") (pinfunction "19_19") (pintype "passive"))
      (node (ref "IC26") (pin "8") (pinfunction "A7_8") (pintype "bidirectional"))
    )
    (net (code "94") (name "PIA-B7") (class "Default")
      (node (ref "CORE-IO") (pin "20") (pinfunction "20_20") (pintype "passive"))
      (node (ref "IC26") (pin "9") (pinfunction "A8_9") (pintype "bidirectional"))
    )
    (net (code "95") (name "Q") (class "Default")
      (node (ref "IC17") (pin "35") (pinfunction "Q_35") (pintype "input"))
      (node (ref "IC2") (pin "12") (pinfunction "Q_12") (pintype "output"))
      (node (ref "IC2") (pin "7") (pinfunction "J_7") (pintype "input"))
    )
    (net (code "96") (name "RX") (class "Default")
      (node (ref "IC20") (pin "12") (pinfunction "R1OUT_12") (pintype "output"))
      (node (ref "IC21") (pin "2") (pinfunction "RXDATA_2") (pintype "input"))
    )
    (net (code "97") (name "RXD") (class "Default")
      (node (ref "COM") (pin "3") (pinfunction "3_3") (pintype "passive"))
      (node (ref "IC20") (pin "13") (pinfunction "R1IN_13") (pintype "input"))
      (node (ref "RS-232") (pin "3") (pinfunction "3_3") (pintype "passive"))
    )
    (net (code "98") (name "R{slash}~{W}") (class "Default")
      (node (ref "EP2") (pin "5") (pinfunction "5_5") (pintype "passive"))
      (node (ref "IC17") (pin "32") (pinfunction "R/~{W}_32") (pintype "output"))
      (node (ref "IC21") (pin "13") (pinfunction "R/~{W}_13") (pintype "input"))
      (node (ref "IC22") (pin "27") (pinfunction "~{WE}_27") (pintype "input"))
      (node (ref "IC24") (pin "21") (pinfunction "R/~{W}_21") (pintype "input"))
    )
    (net (code "99") (name "TX") (class "Default")
      (node (ref "IC20") (pin "11") (pinfunction "T1IN_11") (pintype "input"))
      (node (ref "IC21") (pin "6") (pinfunction "TXDATA_6") (pintype "output"))
    )
    (net (code "100") (name "TXD") (class "Default")
      (node (ref "COM") (pin "2") (pinfunction "2_2") (pintype "passive"))
      (node (ref "IC20") (pin "14") (pinfunction "T1OUT_14") (pintype "output"))
      (node (ref "RS-232") (pin "1") (pinfunction "1_1") (pintype "passive"))
    )
    (net (code "101") (name "VCC") (class "Default")
      (node (ref "BYP17") (pin "1") (pinfunction "1_1") (pintype "passive"))
      (node (ref "BYP18") (pin "1") (pinfunction "1_1") (pintype "passive"))
      (node (ref "BYP19") (pin "1") (pinfunction "1_1") (pintype "passive"))
      (node (ref "BYP2") (pin "1") (pinfunction "1_1") (pintype "passive"))
      (node (ref "BYP20") (pin "1") (pinfunction "1_1") (pintype "passive"))
      (node (ref "BYP21") (pin "1") (pinfunction "1_1") (pintype "passive"))
      (node (ref "BYP22") (pin "1") (pinfunction "1_1") (pintype "passive"))
      (node (ref "BYP23") (pin "1") (pinfunction "1_1") (pintype "passive"))
      (node (ref "BYP24") (pin "1") (pinfunction "1_1") (pintype "passive"))
      (node (ref "BYP25") (pin "1") (pinfunction "1_1") (pintype "passive"))
      (node (ref "BYP26") (pin "1") (pinfunction "1_1") (pintype "passive"))
      (node (ref "BYP27") (pin "1") (pinfunction "1_1") (pintype "passive"))
      (node (ref "BYP28") (pin "1") (pinfunction "1_1") (pintype "passive"))
      (node (ref "BYP29") (pin "1") (pinfunction "1_1") (pintype "passive"))
      (node (ref "C10") (pin "1") (pinfunction "1_1") (pintype "passive"))
      (node (ref "CORE-IO") (pin "12") (pinfunction "12_12") (pintype "passive"))
      (node (ref "CORE-IO") (pin "9") (pinfunction "9_9") (pintype "passive"))
      (node (ref "EP-1") (pin "3") (pinfunction "3_3") (pintype "passive"))
      (node (ref "EP2") (pin "1") (pinfunction "1_1") (pintype "passive"))
      (node (ref "IC17") (pin "7") (pinfunction "VCC_7") (pintype "power_in"))
      (node (ref "IC2") (pin "2") (pinfunction "CL_2") (pintype "input"))
      (node (ref "IC2") (pin "6") (pinfunction "CL_6") (pintype "input"))
      (node (ref "IC21") (pin "10") (pinfunction "CS1_10") (pintype "input"))
      (node (ref "IC21") (pin "12") (pinfunction "VCC_12") (pintype "power_in"))
      (node (ref "IC21") (pin "8") (pinfunction "CS0_8") (pintype "input"))
      (node (ref "IC22") (pin "28") (pinfunction "VCC_28") (pintype "power_in"))
      (node (ref "IC23") (pin "1") (pinfunction "VPP_1") (pintype "input"))
      (node (ref "IC23") (pin "28") (pinfunction "VCC_28") (pintype "power_in"))
      (node (ref "IC24") (pin "20") (pinfunction "VCC_20") (pintype "power_in"))
      (node (ref "IC24") (pin "22") (pinfunction "CS0_22") (pintype "input"))
      (node (ref "IC24") (pin "24") (pinfunction "CS1_24") (pintype "input"))
      (node (ref "IC27") (pin "10") (pinfunction "R_10") (pintype "input"))
      (node (ref "IC27") (pin "14") (pinfunction "V+_14") (pintype "power_in"))
      (node (ref "IC27") (pin "4") (pinfunction "R_4") (pintype "input"))
      (node (ref "JP2") (pin "2") (pinfunction "2_2") (pintype "passive"))
      (node (ref "JP4") (pin "2") (pinfunction "2_2") (pintype "passive"))
      (node (ref "QG1") (pin "14") (pinfunction "VCC_14") (pintype "power_in"))
      (node (ref "R1") (pin "2") (pinfunction "2_2") (pintype "passive"))
      (node (ref "R12") (pin "2") (pinfunction "2_2") (pintype "passive"))
      (node (ref "R14") (pin "2") (pinfunction "2_2") (pintype "passive"))
      (node (ref "R2") (pin "2") (pinfunction "2_2") (pintype "passive"))
      (node (ref "R3") (pin "2") (pinfunction "2_2") (pintype "passive"))
      (node (ref "R5") (pin "2") (pinfunction "2_2") (pintype "passive"))
      (node (ref "R6") (pin "2") (pinfunction "2_2") (pintype "passive"))
      (node (ref "R7") (pin "2") (pinfunction "2_2") (pintype "passive"))
      (node (ref "R8") (pin "2") (pinfunction "2_2") (pintype "passive"))
      (node (ref "R9") (pin "2") (pinfunction "2_2") (pintype "passive"))
    )
    (net (code "102") (name "unconnected-(COM-Pad1)") (class "Default")
      (node (ref "COM") (pin "1") (pinfunction "1_1") (pintype "passive"))
    )
    (net (code "103") (name "unconnected-(COM-Pad9)") (class "Default")
      (node (ref "COM") (pin "9") (pinfunction "9_9") (pintype "passive"))
    )
    (net (code "104") (name "unconnected-(IC17A-AVMA-Pad36)") (class "Default")
      (node (ref "IC17") (pin "36") (pinfunction "AVMA_36") (pintype "output"))
    )
    (net (code "105") (name "unconnected-(IC17A-BA-Pad6)") (class "Default")
      (node (ref "IC17") (pin "6") (pinfunction "BA_6") (pintype "output"))
    )
    (net (code "106") (name "unconnected-(IC17A-BS-Pad5)") (class "Default")
      (node (ref "IC17") (pin "5") (pinfunction "BS_5") (pintype "output"))
    )
    (net (code "107") (name "unconnected-(IC17A-BUSY-Pad33)") (class "Default")
      (node (ref "IC17") (pin "33") (pinfunction "BUSY_33") (pintype "output"))
    )
    (net (code "108") (name "unconnected-(IC17A-LIC-Pad38)") (class "Default")
      (node (ref "IC17") (pin "38") (pinfunction "LIC_38") (pintype "output"))
    )
    (net (code "109") (name "unconnected-(IC19A-Y0-Pad15)") (class "Default")
      (node (ref "IC19") (pin "15") (pinfunction "Y0_15") (pintype "output"))
    )
    (net (code "110") (name "unconnected-(IC19A-Y1-Pad14)") (class "Default")
      (node (ref "IC19") (pin "14") (pinfunction "Y1_14") (pintype "output"))
    )
    (net (code "111") (name "unconnected-(IC19A-Y2-Pad13)") (class "Default")
      (node (ref "IC19") (pin "13") (pinfunction "Y2_13") (pintype "output"))
    )
    (net (code "112") (name "unconnected-(IC19A-Y3-Pad12)") (class "Default")
      (node (ref "IC19") (pin "12") (pinfunction "Y3_12") (pintype "output"))
    )
    (net (code "113") (name "unconnected-(IC19A-Y4-Pad11)") (class "Default")
      (node (ref "IC19") (pin "11") (pinfunction "Y4_11") (pintype "output"))
    )
    (net (code "114") (name "unconnected-(IC19A-Y5-Pad10)") (class "Default")
      (node (ref "IC19") (pin "10") (pinfunction "Y5_10") (pintype "output"))
    )
    (net (code "115") (name "unconnected-(IC20A-R2OUT-Pad9)") (class "Default")
      (node (ref "IC20") (pin "9") (pinfunction "R2OUT_9") (pintype "output"))
    )
    (net (code "116") (name "unconnected-(IC22-NC-Pad1)") (class "Default")
      (node (ref "IC22") (pin "1") (pinfunction "NC_1") (pintype "no_connect"))
    )
    (net (code "117") (name "unconnected-(IC28A-Y1-Pad5)") (class "Default")
      (node (ref "IC28") (pin "5") (pinfunction "Y1_5") (pintype "output"))
    )
    (net (code "118") (name "unconnected-(IC28A-Y2-Pad6)") (class "Default")
      (node (ref "IC28") (pin "6") (pinfunction "Y2_6") (pintype "output"))
    )
    (net (code "119") (name "unconnected-(IC28B-Y0-Pad12)") (class "Default")
      (node (ref "IC28") (pin "12") (pinfunction "Y0_12") (pintype "output"))
    )
    (net (code "120") (name "~{4-B}") (class "Default")
      (node (ref "IC28") (pin "9") (pinfunction "Y3_9") (pintype "output"))
      (node (ref "IC29") (pin "20") (pinfunction "~{CE}_20") (pintype "input"))
      (node (ref "IC29") (pin "22") (pinfunction "~{OE}_22") (pintype "input"))
    )
    (net (code "121") (name "~{0123}") (class "Default")
      (node (ref "IC19") (pin "5") (pinfunction "G2B_5") (pintype "input"))
      (node (ref "IC22") (pin "20") (pinfunction "~{CS1}_20") (pintype "input"))
      (node (ref "IC22") (pin "22") (pinfunction "~{OE}_22") (pintype "input"))
      (node (ref "IC28") (pin "11") (pinfunction "Y1_11") (pintype "output"))
    )
    (net (code "122") (name "~{CDEF}") (class "Default")
      (node (ref "IC23") (pin "20") (pinfunction "~{CE}_20") (pintype "input"))
      (node (ref "IC23") (pin "22") (pinfunction "~{OE}_22") (pintype "input"))
      (node (ref "IC28") (pin "10") (pinfunction "Y2_10") (pintype "output"))
    )
    (net (code "123") (name "~{EP1}") (class "Default")
      (node (ref "IC28") (pin "14") (pinfunction "A_14") (pintype "input"))
      (node (ref "IC28") (pin "7") (pinfunction "Y3_7") (pintype "output"))
    )
    (net (code "124") (name "~{FIRQ}") (class "Default")
      (node (ref "IC17") (pin "4") (pinfunction "FIRQ_4") (pintype "input"))
      (node (ref "IC24") (pin "37") (pinfunction "IRQB_37") (pintype "open_collector"))
      (node (ref "IC24") (pin "38") (pinfunction "IRQA_38") (pintype "open_collector"))
      (node (ref "R8") (pin "1") (pinfunction "1_1") (pintype "passive"))
    )
    (net (code "125") (name "~{HLT}") (class "Default")
      (node (ref "IC17") (pin "40") (pinfunction "HALT_40") (pintype "input"))
      (node (ref "R5") (pin "1") (pinfunction "1_1") (pintype "passive"))
    )
    (net (code "126") (name "~{IO-E}") (class "Default")
      (node (ref "IC19") (pin "9") (pinfunction "Y6_9") (pintype "output"))
      (node (ref "IC24") (pin "23") (pinfunction "CS2_23") (pintype "input"))
    )
    (net (code "127") (name "~{IO-F}") (class "Default")
      (node (ref "IC19") (pin "7") (pinfunction "Y7_7") (pintype "output"))
      (node (ref "IC21") (pin "9") (pinfunction "CS2_9") (pintype "input"))
    )
    (net (code "128") (name "~{IRQ}") (class "Default")
      (node (ref "IC17") (pin "3") (pinfunction "IRQ_3") (pintype "input"))
      (node (ref "IC21") (pin "7") (pinfunction "IRQ_7") (pintype "output"))
      (node (ref "R7") (pin "1") (pinfunction "1_1") (pintype "passive"))
    )
    (net (code "129") (name "~{NMI}") (class "Default")
      (node (ref "IC17") (pin "2") (pinfunction "NMI_2") (pintype "input"))
      (node (ref "R6") (pin "1") (pinfunction "1_1") (pintype "passive"))
    )
    (net (code "130") (name "~{RST}") (class "Default")
      (node (ref "IC17") (pin "37") (pinfunction "RESET_37") (pintype "input"))
      (node (ref "IC18") (pin "6") (pinfunction "O_6") (pintype "output"))
      (node (ref "IC24") (pin "34") (pinfunction "RESET_34") (pintype "input"))
    )
  )
)
